# main.net
KiCad netlist of a schematic drawn in EAGLE
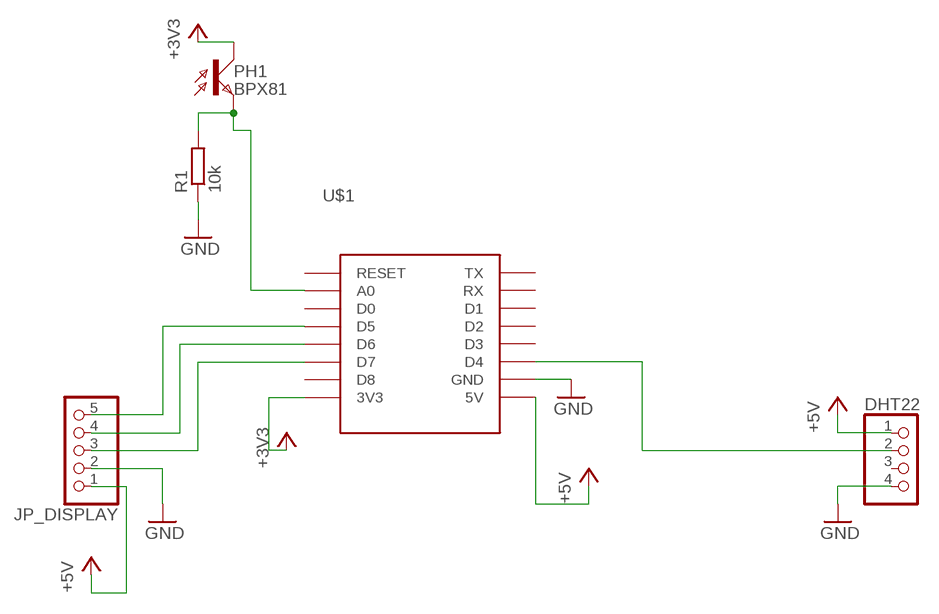
[diagram p0: schematic, sheet 1]

(export (version "E")
  (design (tool "Eeschema 10.0.6"))
  (components
    (comp (ref "DHT22")
      (value "PINHD-1X4/90")
      (footprint "eagle-import:1X04_90")
      (libsource (lib "eagle-import") (part "PINHD-1X4/90"))
    )
    (comp (ref "JP_DISPLAY")
      (value "PINHD-1X5/90")
      (footprint "eagle-import:1X05_90")
      (libsource (lib "eagle-import") (part "PINHD-1X5/90"))
    )
    (comp (ref "PH1")
      (value "BPX81")
      (footprint "eagle-import:BPX81")
      (libsource (lib "eagle-import") (part "BPX81"))
    )
    (comp (ref "R1")
      (value "10k")
      (footprint "eagle-import:R0805")
      (libsource (lib "eagle-import") (part "R-EU_R0805"))
    )
    (comp (ref "U$1")
      (value "WEMOS-D1-MINI")
      (footprint "eagle-import:WEMOS-D1-MINI")
      (libsource (lib "eagle-import") (part "WEMOS-D1-MINI"))
    )
  )
  (nets
    (net (code "1") (name "+3V3") (class "Default")
      (node (ref "PH1") (pin "C") (pinfunction "C_C") (pintype "passive"))
      (node (ref "U$1") (pin "3V3") (pinfunction "3V3_3V3") (pintype "bidirectional"))
    )
    (net (code "2") (name "+5V") (class "Default")
      (node (ref "DHT22") (pin "1") (pinfunction "1_1") (pintype "passive"))
      (node (ref "JP_DISPLAY") (pin "1") (pinfunction "1_1") (pintype "passive"))
      (node (ref "U$1") (pin "5V") (pinfunction "5V_5V") (pintype "bidirectional"))
    )
    (net (code "3") (name "GND") (class "Default")
      (node (ref "DHT22") (pin "4") (pinfunction "4_4") (pintype "passive"))
      (node (ref "JP_DISPLAY") (pin "2") (pinfunction "2_2") (pintype "passive"))
      (node (ref "R1") (pin "1") (pinfunction "1_1") (pintype "passive"))
      (node (ref "U$1") (pin "GND") (pinfunction "GND_GND") (pintype "bidirectional"))
    )
    (net (code "4") (name "Net-(DHT22-Pad2)") (class "Default")
      (node (ref "DHT22") (pin "2") (pinfunction "2_2") (pintype "passive"))
      (node (ref "U$1") (pin "D4") (pinfunction "D4_D4") (pintype "bidirectional"))
    )
    (net (code "5") (name "Net-(JP_DISPLAY-Pad3)") (class "Default")
      (node (ref "JP_DISPLAY") (pin "3") (pinfunction "3_3") (pintype "passive"))
      (node (ref "U$1") (pin "D7") (pinfunction "D7_D7") (pintype "bidirectional"))
    )
    (net (code "6") (name "Net-(JP_DISPLAY-Pad4)") (class "Default")
      (node (ref "JP_DISPLAY") (pin "4") (pinfunction "4_4") (pintype "passive"))
      (node (ref "U$1") (pin "D6") (pinfunction "D6_D6") (pintype "bidirectional"))
    )
    (net (code "7") (name "Net-(JP_DISPLAY-Pad5)") (class "Default")
      (node (ref "JP_DISPLAY") (pin "5") (pinfunction "5_5") (pintype "passive"))
      (node (ref "U$1") (pin "D5") (pinfunction "D5_D5") (pintype "bidirectional"))
    )
    (net (code "8") (name "Net-(PH1-PadE)") (class "Default")
      (node (ref "PH1") (pin "E") (pinfunction "E_E") (pintype "passive"))
      (node (ref "R1") (pin "2") (pinfunction "2_2") (pintype "passive"))
      (node (ref "U$1") (pin "A0") (pinfunction "A0_A0") (pintype "bidirectional"))
    )
    (net (code "9") (name "unconnected-(DHT22-Pad3)") (class "Default")
      (node (ref "DHT22") (pin "3") (pinfunction "3_3") (pintype "passive"))
    )
    (net (code "10") (name "unconnected-(U$1-PadD0)") (class "Default")
      (node (ref "U$1") (pin "D0") (pinfunction "D0_D0") (pintype "bidirectional"))
    )
    (net (code "11") (name "unconnected-(U$1-PadD1)") (class "Default")
      (node (ref "U$1") (pin "D1") (pinfunction "D1_D1") (pintype "bidirectional"))
    )
    (net (code "12") (name "unconnected-(U$1-PadD2)") (class "Default")
      (node (ref "U$1") (pin "D2") (pinfunction "D2_D2") (pintype "bidirectional"))
    )
    (net (code "13") (name "unconnected-(U$1-PadD3)") (class "Default")
      (node (ref "U$1") (pin "D3") (pinfunction "D3_D3") (pintype "bidirectional"))
    )
    (net (code "14") (name "unconnected-(U$1-PadD8)") (class "Default")
      (node (ref "U$1") (pin "D8") (pinfunction "D8_D8") (pintype "bidirectional"))
    )
    (net (code "15") (name "unconnected-(U$1-PadRESET)") (class "Default")
      (node (ref "U$1") (pin "RESET") (pinfunction "RESET_RESET") (pintype "bidirectional"))
    )
    (net (code "16") (name "unconnected-(U$1-PadRX)") (class "Default")
      (node (ref "U$1") (pin "RX") (pinfunction "RX_RX") (pintype "bidirectional"))
    )
    (net (code "17") (name "unconnected-(U$1-PadTX)") (class "Default")
      (node (ref "U$1") (pin "TX") (pinfunction "TX_TX") (pintype "bidirectional"))
    )
  )
)
